# codec.net
KiCad netlist of a schematic drawn in EAGLE
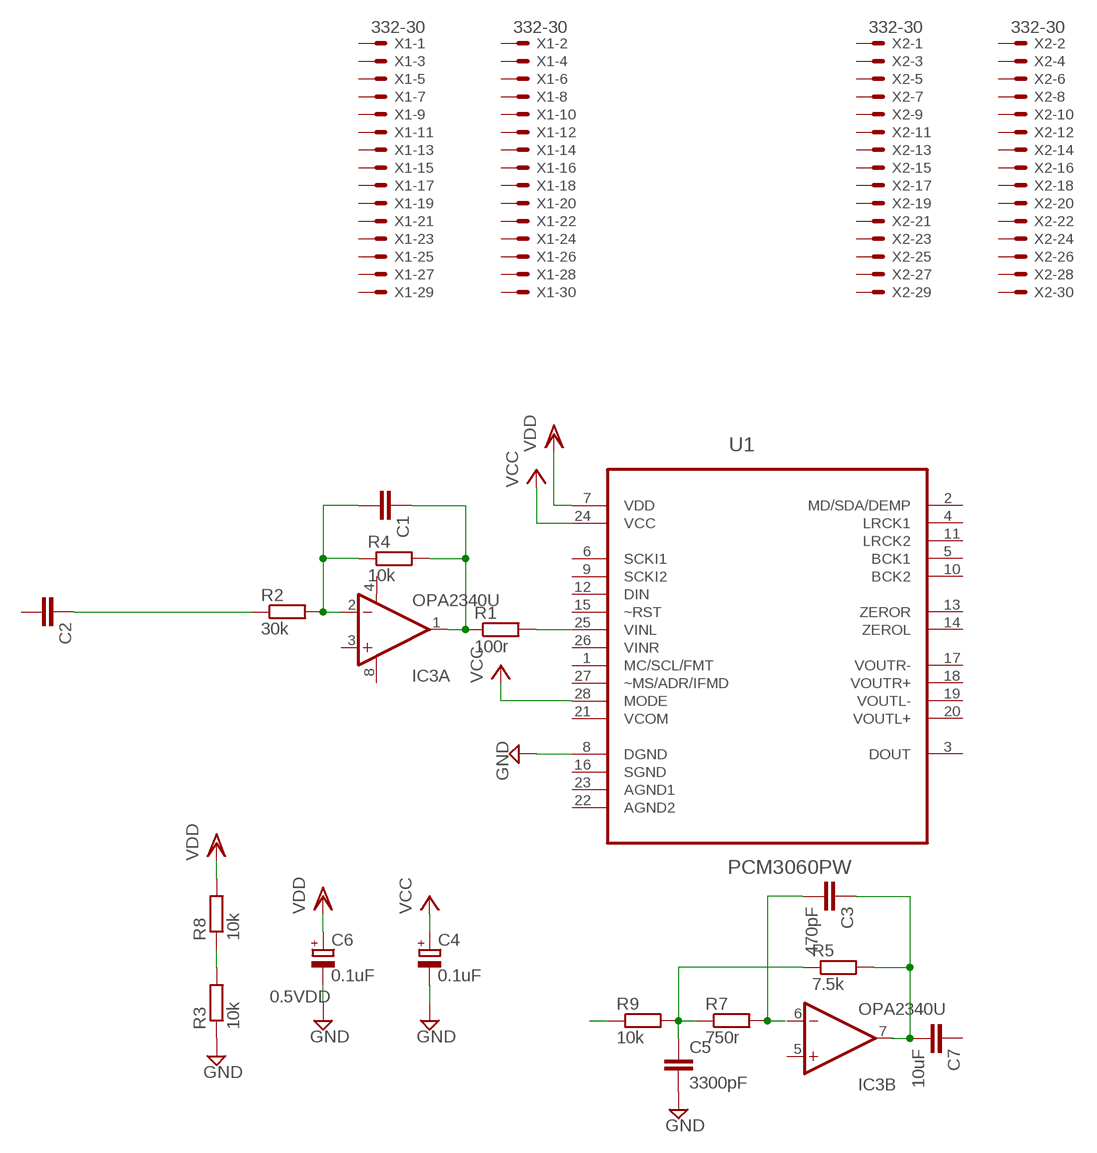
[diagram p0: schematic, sheet 1]

(export (version "E")
  (design (tool "Eeschema 10.0.6"))
  (components
    (comp (ref "C1")
      (value "C-EUC1608")
      (footprint "eagle-import:C1608")
      (libsource (lib "eagle-import") (part "C-EUC1608"))
    )
    (comp (ref "C2")
      (value "C-EUC1608")
      (footprint "eagle-import:C1608")
      (libsource (lib "eagle-import") (part "C-EUC1608"))
    )
    (comp (ref "C3")
      (value "470pF")
      (footprint "eagle-import:C1608")
      (libsource (lib "eagle-import") (part "C-EUC1608"))
    )
    (comp (ref "C4")
      (value "0.1uF")
      (footprint "eagle-import:150CLZ-1010")
      (libsource (lib "eagle-import") (part "CPOL-EU150CLZ-1010"))
    )
    (comp (ref "C5")
      (value "3300pF")
      (footprint "eagle-import:C1608")
      (libsource (lib "eagle-import") (part "C-EUC1608"))
    )
    (comp (ref "C6")
      (value "0.1uF")
      (footprint "eagle-import:150CLZ-1010")
      (libsource (lib "eagle-import") (part "CPOL-EU150CLZ-1010"))
    )
    (comp (ref "C7")
      (value "10uF")
      (footprint "eagle-import:C1608")
      (libsource (lib "eagle-import") (part "C-EUC1608"))
    )
    (comp (ref "IC3")
      (value "OPA2340U")
      (footprint "eagle-import:SO08")
      (fields (field (name "MF") "TEXAS INSTRUMENTS") (field (name "MPN") "OPA2340UA"))
      (libsource (lib "eagle-import") (part "OPA2340U"))
    )
    (comp (ref "R1")
      (value "100r")
      (footprint "eagle-import:R1206")
      (libsource (lib "eagle-import") (part "R-EU_R1206"))
    )
    (comp (ref "R2")
      (value "30k")
      (footprint "eagle-import:R1206")
      (libsource (lib "eagle-import") (part "R-EU_R1206"))
    )
    (comp (ref "R3")
      (value "10k")
      (footprint "eagle-import:R1206")
      (libsource (lib "eagle-import") (part "R-EU_R1206"))
    )
    (comp (ref "R4")
      (value "10k")
      (footprint "eagle-import:R1206")
      (libsource (lib "eagle-import") (part "R-EU_R1206"))
    )
    (comp (ref "R5")
      (value "7.5k")
      (footprint "eagle-import:R1206")
      (libsource (lib "eagle-import") (part "R-EU_R1206"))
    )
    (comp (ref "R7")
      (value "750r")
      (footprint "eagle-import:R1206")
      (libsource (lib "eagle-import") (part "R-EU_R1206"))
    )
    (comp (ref "R8")
      (value "10k")
      (footprint "eagle-import:R1206")
      (libsource (lib "eagle-import") (part "R-EU_R1206"))
    )
    (comp (ref "R9")
      (value "10k")
      (footprint "eagle-import:R1206")
      (libsource (lib "eagle-import") (part "R-EU_R1206"))
    )
    (comp (ref "U1")
      (value "PCM3060PW")
      (footprint "eagle-import:SOP65P640X120-28N")
      (libsource (lib "eagle-import") (part "PCM3060PW"))
    )
    (comp (ref "X1")
      (value "332-30")
      (footprint "eagle-import:332-30")
      (libsource (lib "eagle-import") (part "332-30"))
    )
    (comp (ref "X2")
      (value "332-30")
      (footprint "eagle-import:332-30")
      (libsource (lib "eagle-import") (part "332-30"))
    )
  )
  (nets
    (net (code "1") (name "/0.5VDD") (class "Default")
      (node (ref "R3") (pin "2") (pinfunction "2_2") (pintype "passive"))
      (node (ref "R8") (pin "1") (pinfunction "1_1") (pintype "passive"))
    )
    (net (code "2") (name "/V+") (class "Default")
      (node (ref "IC3") (pin "8") (pinfunction "V+_8") (pintype "power_in"))
    )
    (net (code "3") (name "/V-") (class "Default")
      (node (ref "IC3") (pin "4") (pinfunction "V-_4") (pintype "power_in"))
    )
    (net (code "4") (name "GND") (class "Default")
      (node (ref "C4") (pin "-") (pinfunction "-_-") (pintype "passive"))
      (node (ref "C5") (pin "2") (pinfunction "2_2") (pintype "passive"))
      (node (ref "C6") (pin "-") (pinfunction "-_-") (pintype "passive"))
      (node (ref "R3") (pin "1") (pinfunction "1_1") (pintype "passive"))
      (node (ref "U1") (pin "8") (pinfunction "DGND_8") (pintype "passive"))
    )
    (net (code "5") (name "Net-(C2-Pad1)") (class "Default")
      (node (ref "C2") (pin "1") (pinfunction "1_1") (pintype "passive"))
      (node (ref "R2") (pin "1") (pinfunction "1_1") (pintype "passive"))
    )
    (net (code "6") (name "Net-(C3-Pad2)") (class "Default")
      (node (ref "C3") (pin "2") (pinfunction "2_2") (pintype "passive"))
      (node (ref "R7") (pin "2") (pinfunction "2_2") (pintype "passive"))
    )
    (net (code "7") (name "Net-(C5-Pad1)") (class "Default")
      (node (ref "C5") (pin "1") (pinfunction "1_1") (pintype "passive"))
      (node (ref "R5") (pin "1") (pinfunction "1_1") (pintype "passive"))
      (node (ref "R7") (pin "1") (pinfunction "1_1") (pintype "passive"))
      (node (ref "R9") (pin "2") (pinfunction "2_2") (pintype "passive"))
    )
    (net (code "8") (name "Net-(IC3A--IN)") (class "Default")
      (node (ref "C1") (pin "2") (pinfunction "2_2") (pintype "passive"))
      (node (ref "IC3") (pin "2") (pinfunction "-IN_2") (pintype "input"))
      (node (ref "R2") (pin "2") (pinfunction "2_2") (pintype "passive"))
      (node (ref "R4") (pin "1") (pinfunction "1_1") (pintype "passive"))
    )
    (net (code "9") (name "Net-(IC3A-OUT)") (class "Default")
      (node (ref "C1") (pin "1") (pinfunction "1_1") (pintype "passive"))
      (node (ref "IC3") (pin "1") (pinfunction "OUT_1") (pintype "output"))
      (node (ref "R1") (pin "1") (pinfunction "1_1") (pintype "passive"))
      (node (ref "R4") (pin "2") (pinfunction "2_2") (pintype "passive"))
    )
    (net (code "10") (name "Net-(IC3B-OUT)") (class "Default")
      (node (ref "C3") (pin "1") (pinfunction "1_1") (pintype "passive"))
      (node (ref "C7") (pin "2") (pinfunction "2_2") (pintype "passive"))
      (node (ref "IC3") (pin "7") (pinfunction "OUT_7") (pintype "output"))
      (node (ref "R5") (pin "2") (pinfunction "2_2") (pintype "passive"))
    )
    (net (code "11") (name "Net-(U1-VINL)") (class "Default")
      (node (ref "R1") (pin "2") (pinfunction "2_2") (pintype "passive"))
      (node (ref "U1") (pin "25") (pinfunction "VINL_25") (pintype "input"))
    )
    (net (code "12") (name "VCC") (class "Default")
      (node (ref "C4") (pin "+") (pinfunction "+_+") (pintype "passive"))
      (node (ref "U1") (pin "24") (pinfunction "VCC_24") (pintype "power_in"))
      (node (ref "U1") (pin "28") (pinfunction "MODE_28") (pintype "input"))
    )
    (net (code "13") (name "VDD") (class "Default")
      (node (ref "C6") (pin "+") (pinfunction "+_+") (pintype "passive"))
      (node (ref "R8") (pin "2") (pinfunction "2_2") (pintype "passive"))
      (node (ref "U1") (pin "7") (pinfunction "VDD_7") (pintype "power_in"))
    )
    (net (code "14") (name "unconnected-(C2-Pad2)") (class "Default")
      (node (ref "C2") (pin "2") (pinfunction "2_2") (pintype "passive"))
    )
    (net (code "15") (name "unconnected-(C7-Pad1)") (class "Default")
      (node (ref "C7") (pin "1") (pinfunction "1_1") (pintype "passive"))
    )
    (net (code "16") (name "unconnected-(IC3A-+IN-Pad3)") (class "Default")
      (node (ref "IC3") (pin "3") (pinfunction "+IN_3") (pintype "input"))
    )
    (net (code "17") (name "unconnected-(IC3B-+IN-Pad5)") (class "Default")
      (node (ref "IC3") (pin "5") (pinfunction "+IN_5") (pintype "input"))
    )
    (net (code "18") (name "unconnected-(IC3B--IN-Pad6)") (class "Default")
      (node (ref "IC3") (pin "6") (pinfunction "-IN_6") (pintype "input"))
    )
    (net (code "19") (name "unconnected-(R9-Pad1)") (class "Default")
      (node (ref "R9") (pin "1") (pinfunction "1_1") (pintype "passive"))
    )
    (net (code "20") (name "unconnected-(U1-AGND1-Pad23)") (class "Default")
      (node (ref "U1") (pin "23") (pinfunction "AGND1_23") (pintype "passive"))
    )
    (net (code "21") (name "unconnected-(U1-AGND2-Pad22)") (class "Default")
      (node (ref "U1") (pin "22") (pinfunction "AGND2_22") (pintype "passive"))
    )
    (net (code "22") (name "unconnected-(U1-BCK1-Pad5)") (class "Default")
      (node (ref "U1") (pin "5") (pinfunction "BCK1_5") (pintype "bidirectional"))
    )
    (net (code "23") (name "unconnected-(U1-BCK2-Pad10)") (class "Default")
      (node (ref "U1") (pin "10") (pinfunction "BCK2_10") (pintype "bidirectional"))
    )
    (net (code "24") (name "unconnected-(U1-DIN-Pad12)") (class "Default")
      (node (ref "U1") (pin "12") (pinfunction "DIN_12") (pintype "input"))
    )
    (net (code "25") (name "unconnected-(U1-DOUT-Pad3)") (class "Default")
      (node (ref "U1") (pin "3") (pinfunction "DOUT_3") (pintype "output"))
    )
    (net (code "26") (name "unconnected-(U1-LRCK1-Pad4)") (class "Default")
      (node (ref "U1") (pin "4") (pinfunction "LRCK1_4") (pintype "bidirectional"))
    )
    (net (code "27") (name "unconnected-(U1-LRCK2-Pad11)") (class "Default")
      (node (ref "U1") (pin "11") (pinfunction "LRCK2_11") (pintype "bidirectional"))
    )
    (net (code "28") (name "unconnected-(U1-MC{slash}SCL{slash}FMT-Pad1)") (class "Default")
      (node (ref "U1") (pin "1") (pinfunction "MC/SCL/FMT_1") (pintype "input"))
    )
    (net (code "29") (name "unconnected-(U1-MD{slash}SDA{slash}DEMP-Pad2)") (class "Default")
      (node (ref "U1") (pin "2") (pinfunction "MD/SDA/DEMP_2") (pintype "bidirectional"))
    )
    (net (code "30") (name "unconnected-(U1-SCKI1-Pad6)") (class "Default")
      (node (ref "U1") (pin "6") (pinfunction "SCKI1_6") (pintype "input"))
    )
    (net (code "31") (name "unconnected-(U1-SCKI2-Pad9)") (class "Default")
      (node (ref "U1") (pin "9") (pinfunction "SCKI2_9") (pintype "input"))
    )
    (net (code "32") (name "unconnected-(U1-SGND-Pad16)") (class "Default")
      (node (ref "U1") (pin "16") (pinfunction "SGND_16") (pintype "passive"))
    )
    (net (code "33") (name "unconnected-(U1-VCOM-Pad21)") (class "Default")
      (node (ref "U1") (pin "21") (pinfunction "VCOM_21") (pintype "passive"))
    )
    (net (code "34") (name "unconnected-(U1-VINR-Pad26)") (class "Default")
      (node (ref "U1") (pin "26") (pinfunction "VINR_26") (pintype "input"))
    )
    (net (code "35") (name "unconnected-(U1-VOUTL+-Pad20)") (class "Default")
      (node (ref "U1") (pin "20") (pinfunction "VOUTL+_20") (pintype "output"))
    )
    (net (code "36") (name "unconnected-(U1-VOUTL--Pad19)") (class "Default")
      (node (ref "U1") (pin "19") (pinfunction "VOUTL-_19") (pintype "output"))
    )
    (net (code "37") (name "unconnected-(U1-VOUTR+-Pad18)") (class "Default")
      (node (ref "U1") (pin "18") (pinfunction "VOUTR+_18") (pintype "output"))
    )
    (net (code "38") (name "unconnected-(U1-VOUTR--Pad17)") (class "Default")
      (node (ref "U1") (pin "17") (pinfunction "VOUTR-_17") (pintype "output"))
    )
    (net (code "39") (name "unconnected-(U1-ZEROL-Pad14)") (class "Default")
      (node (ref "U1") (pin "14") (pinfunction "ZEROL_14") (pintype "output"))
    )
    (net (code "40") (name "unconnected-(U1-ZEROR-Pad13)") (class "Default")
      (node (ref "U1") (pin "13") (pinfunction "ZEROR_13") (pintype "output"))
    )
    (net (code "41") (name "unconnected-(U1-~{MS{slash}ADR{slash}IFMD}-Pad27)") (class "Default")
      (node (ref "U1") (pin "27") (pinfunction "~{MS/ADR/IFMD}_27") (pintype "input"))
    )
    (net (code "42") (name "unconnected-(U1-~{RST}-Pad15)") (class "Default")
      (node (ref "U1") (pin "15") (pinfunction "~{RST}_15") (pintype "input"))
    )
    (net (code "43") (name "unconnected-(X1A-S-Pad1)") (class "Default")
      (node (ref "X1") (pin "1") (pinfunction "S_1") (pintype "passive"))
    )
    (net (code "44") (name "unconnected-(X1AA-S-Pad6)") (class "Default")
      (node (ref "X1") (pin "6") (pinfunction "S_6") (pintype "passive"))
    )
    (net (code "45") (name "unconnected-(X1AB-S-Pad7)") (class "Default")
      (node (ref "X1") (pin "7") (pinfunction "S_7") (pintype "passive"))
    )
    (net (code "46") (name "unconnected-(X1AC-S-Pad8)") (class "Default")
      (node (ref "X1") (pin "8") (pinfunction "S_8") (pintype "passive"))
    )
    (net (code "47") (name "unconnected-(X1AD-S-Pad9)") (class "Default")
      (node (ref "X1") (pin "9") (pinfunction "S_9") (pintype "passive"))
    )
    (net (code "48") (name "unconnected-(X1B-S-Pad10)") (class "Default")
      (node (ref "X1") (pin "10") (pinfunction "S_10") (pintype "passive"))
    )
    (net (code "49") (name "unconnected-(X1C-S-Pad11)") (class "Default")
      (node (ref "X1") (pin "11") (pinfunction "S_11") (pintype "passive"))
    )
    (net (code "50") (name "unconnected-(X1D-S-Pad12)") (class "Default")
      (node (ref "X1") (pin "12") (pinfunction "S_12") (pintype "passive"))
    )
    (net (code "51") (name "unconnected-(X1E-S-Pad13)") (class "Default")
      (node (ref "X1") (pin "13") (pinfunction "S_13") (pintype "passive"))
    )
    (net (code "52") (name "unconnected-(X1F-S-Pad14)") (class "Default")
      (node (ref "X1") (pin "14") (pinfunction "S_14") (pintype "passive"))
    )
    (net (code "53") (name "unconnected-(X1G-S-Pad15)") (class "Default")
      (node (ref "X1") (pin "15") (pinfunction "S_15") (pintype "passive"))
    )
    (net (code "54") (name "unconnected-(X1H-S-Pad16)") (class "Default")
      (node (ref "X1") (pin "16") (pinfunction "S_16") (pintype "passive"))
    )
    (net (code "55") (name "unconnected-(X1I-S-Pad17)") (class "Default")
      (node (ref "X1") (pin "17") (pinfunction "S_17") (pintype "passive"))
    )
    (net (code "56") (name "unconnected-(X1J-S-Pad18)") (class "Default")
      (node (ref "X1") (pin "18") (pinfunction "S_18") (pintype "passive"))
    )
    (net (code "57") (name "unconnected-(X1K-S-Pad19)") (class "Default")
      (node (ref "X1") (pin "19") (pinfunction "S_19") (pintype "passive"))
    )
    (net (code "58") (name "unconnected-(X1L-S-Pad2)") (class "Default")
      (node (ref "X1") (pin "2") (pinfunction "S_2") (pintype "passive"))
    )
    (net (code "59") (name "unconnected-(X1M-S-Pad20)") (class "Default")
      (node (ref "X1") (pin "20") (pinfunction "S_20") (pintype "passive"))
    )
    (net (code "60") (name "unconnected-(X1N-S-Pad21)") (class "Default")
      (node (ref "X1") (pin "21") (pinfunction "S_21") (pintype "passive"))
    )
    (net (code "61") (name "unconnected-(X1O-S-Pad22)") (class "Default")
      (node (ref "X1") (pin "22") (pinfunction "S_22") (pintype "passive"))
    )
    (net (code "62") (name "unconnected-(X1P-S-Pad23)") (class "Default")
      (node (ref "X1") (pin "23") (pinfunction "S_23") (pintype "passive"))
    )
    (net (code "63") (name "unconnected-(X1Q-S-Pad24)") (class "Default")
      (node (ref "X1") (pin "24") (pinfunction "S_24") (pintype "passive"))
    )
    (net (code "64") (name "unconnected-(X1R-S-Pad25)") (class "Default")
      (node (ref "X1") (pin "25") (pinfunction "S_25") (pintype "passive"))
    )
    (net (code "65") (name "unconnected-(X1S-S-Pad26)") (class "Default")
      (node (ref "X1") (pin "26") (pinfunction "S_26") (pintype "passive"))
    )
    (net (code "66") (name "unconnected-(X1T-S-Pad27)") (class "Default")
      (node (ref "X1") (pin "27") (pinfunction "S_27") (pintype "passive"))
    )
    (net (code "67") (name "unconnected-(X1U-S-Pad28)") (class "Default")
      (node (ref "X1") (pin "28") (pinfunction "S_28") (pintype "passive"))
    )
    (net (code "68") (name "unconnected-(X1V-S-Pad29)") (class "Default")
      (node (ref "X1") (pin "29") (pinfunction "S_29") (pintype "passive"))
    )
    (net (code "69") (name "unconnected-(X1W-S-Pad3)") (class "Default")
      (node (ref "X1") (pin "3") (pinfunction "S_3") (pintype "passive"))
    )
    (net (code "70") (name "unconnected-(X1X-S-Pad30)") (class "Default")
      (node (ref "X1") (pin "30") (pinfunction "S_30") (pintype "passive"))
    )
    (net (code "71") (name "unconnected-(X1Y-S-Pad4)") (class "Default")
      (node (ref "X1") (pin "4") (pinfunction "S_4") (pintype "passive"))
    )
    (net (code "72") (name "unconnected-(X1Z-S-Pad5)") (class "Default")
      (node (ref "X1") (pin "5") (pinfunction "S_5") (pintype "passive"))
    )
    (net (code "73") (name "unconnected-(X2A-S-Pad1)") (class "Default")
      (node (ref "X2") (pin "1") (pinfunction "S_1") (pintype "passive"))
    )
    (net (code "74") (name "unconnected-(X2AA-S-Pad6)") (class "Default")
      (node (ref "X2") (pin "6") (pinfunction "S_6") (pintype "passive"))
    )
    (net (code "75") (name "unconnected-(X2AB-S-Pad7)") (class "Default")
      (node (ref "X2") (pin "7") (pinfunction "S_7") (pintype "passive"))
    )
    (net (code "76") (name "unconnected-(X2AC-S-Pad8)") (class "Default")
      (node (ref "X2") (pin "8") (pinfunction "S_8") (pintype "passive"))
    )
    (net (code "77") (name "unconnected-(X2AD-S-Pad9)") (class "Default")
      (node (ref "X2") (pin "9") (pinfunction "S_9") (pintype "passive"))
    )
    (net (code "78") (name "unconnected-(X2B-S-Pad10)") (class "Default")
      (node (ref "X2") (pin "10") (pinfunction "S_10") (pintype "passive"))
    )
    (net (code "79") (name "unconnected-(X2C-S-Pad11)") (class "Default")
      (node (ref "X2") (pin "11") (pinfunction "S_11") (pintype "passive"))
    )
    (net (code "80") (name "unconnected-(X2D-S-Pad12)") (class "Default")
      (node (ref "X2") (pin "12") (pinfunction "S_12") (pintype "passive"))
    )
    (net (code "81") (name "unconnected-(X2E-S-Pad13)") (class "Default")
      (node (ref "X2") (pin "13") (pinfunction "S_13") (pintype "passive"))
    )
    (net (code "82") (name "unconnected-(X2F-S-Pad14)") (class "Default")
      (node (ref "X2") (pin "14") (pinfunction "S_14") (pintype "passive"))
    )
    (net (code "83") (name "unconnected-(X2G-S-Pad15)") (class "Default")
      (node (ref "X2") (pin "15") (pinfunction "S_15") (pintype "passive"))
    )
    (net (code "84") (name "unconnected-(X2H-S-Pad16)") (class "Default")
      (node (ref "X2") (pin "16") (pinfunction "S_16") (pintype "passive"))
    )
    (net (code "85") (name "unconnected-(X2I-S-Pad17)") (class "Default")
      (node (ref "X2") (pin "17") (pinfunction "S_17") (pintype "passive"))
    )
    (net (code "86") (name "unconnected-(X2J-S-Pad18)") (class "Default")
      (node (ref "X2") (pin "18") (pinfunction "S_18") (pintype "passive"))
    )
    (net (code "87") (name "unconnected-(X2K-S-Pad19)") (class "Default")
      (node (ref "X2") (pin "19") (pinfunction "S_19") (pintype "passive"))
    )
    (net (code "88") (name "unconnected-(X2L-S-Pad2)") (class "Default")
      (node (ref "X2") (pin "2") (pinfunction "S_2") (pintype "passive"))
    )
    (net (code "89") (name "unconnected-(X2M-S-Pad20)") (class "Default")
      (node (ref "X2") (pin "20") (pinfunction "S_20") (pintype "passive"))
    )
    (net (code "90") (name "unconnected-(X2N-S-Pad21)") (class "Default")
      (node (ref "X2") (pin "21") (pinfunction "S_21") (pintype "passive"))
    )
    (net (code "91") (name "unconnected-(X2O-S-Pad22)") (class "Default")
      (node (ref "X2") (pin "22") (pinfunction "S_22") (pintype "passive"))
    )
    (net (code "92") (name "unconnected-(X2P-S-Pad23)") (class "Default")
      (node (ref "X2") (pin "23") (pinfunction "S_23") (pintype "passive"))
    )
    (net (code "93") (name "unconnected-(X2Q-S-Pad24)") (class "Default")
      (node (ref "X2") (pin "24") (pinfunction "S_24") (pintype "passive"))
    )
    (net (code "94") (name "unconnected-(X2R-S-Pad25)") (class "Default")
      (node (ref "X2") (pin "25") (pinfunction "S_25") (pintype "passive"))
    )
    (net (code "95") (name "unconnected-(X2S-S-Pad26)") (class "Default")
      (node (ref "X2") (pin "26") (pinfunction "S_26") (pintype "passive"))
    )
    (net (code "96") (name "unconnected-(X2T-S-Pad27)") (class "Default")
      (node (ref "X2") (pin "27") (pinfunction "S_27") (pintype "passive"))
    )
    (net (code "97") (name "unconnected-(X2U-S-Pad28)") (class "Default")
      (node (ref "X2") (pin "28") (pinfunction "S_28") (pintype "passive"))
    )
    (net (code "98") (name "unconnected-(X2V-S-Pad29)") (class "Default")
      (node (ref "X2") (pin "29") (pinfunction "S_29") (pintype "passive"))
    )
    (net (code "99") (name "unconnected-(X2W-S-Pad3)") (class "Default")
      (node (ref "X2") (pin "3") (pinfunction "S_3") (pintype "passive"))
    )
    (net (code "100") (name "unconnected-(X2X-S-Pad30)") (class "Default")
      (node (ref "X2") (pin "30") (pinfunction "S_30") (pintype "passive"))
    )
    (net (code "101") (name "unconnected-(X2Y-S-Pad4)") (class "Default")
      (node (ref "X2") (pin "4") (pinfunction "S_4") (pintype "passive"))
    )
    (net (code "102") (name "unconnected-(X2Z-S-Pad5)") (class "Default")
      (node (ref "X2") (pin "5") (pinfunction "S_5") (pintype "passive"))
    )
  )
)
